# Motherboard_V3_1.net
KiCad netlist of a schematic drawn in EAGLE
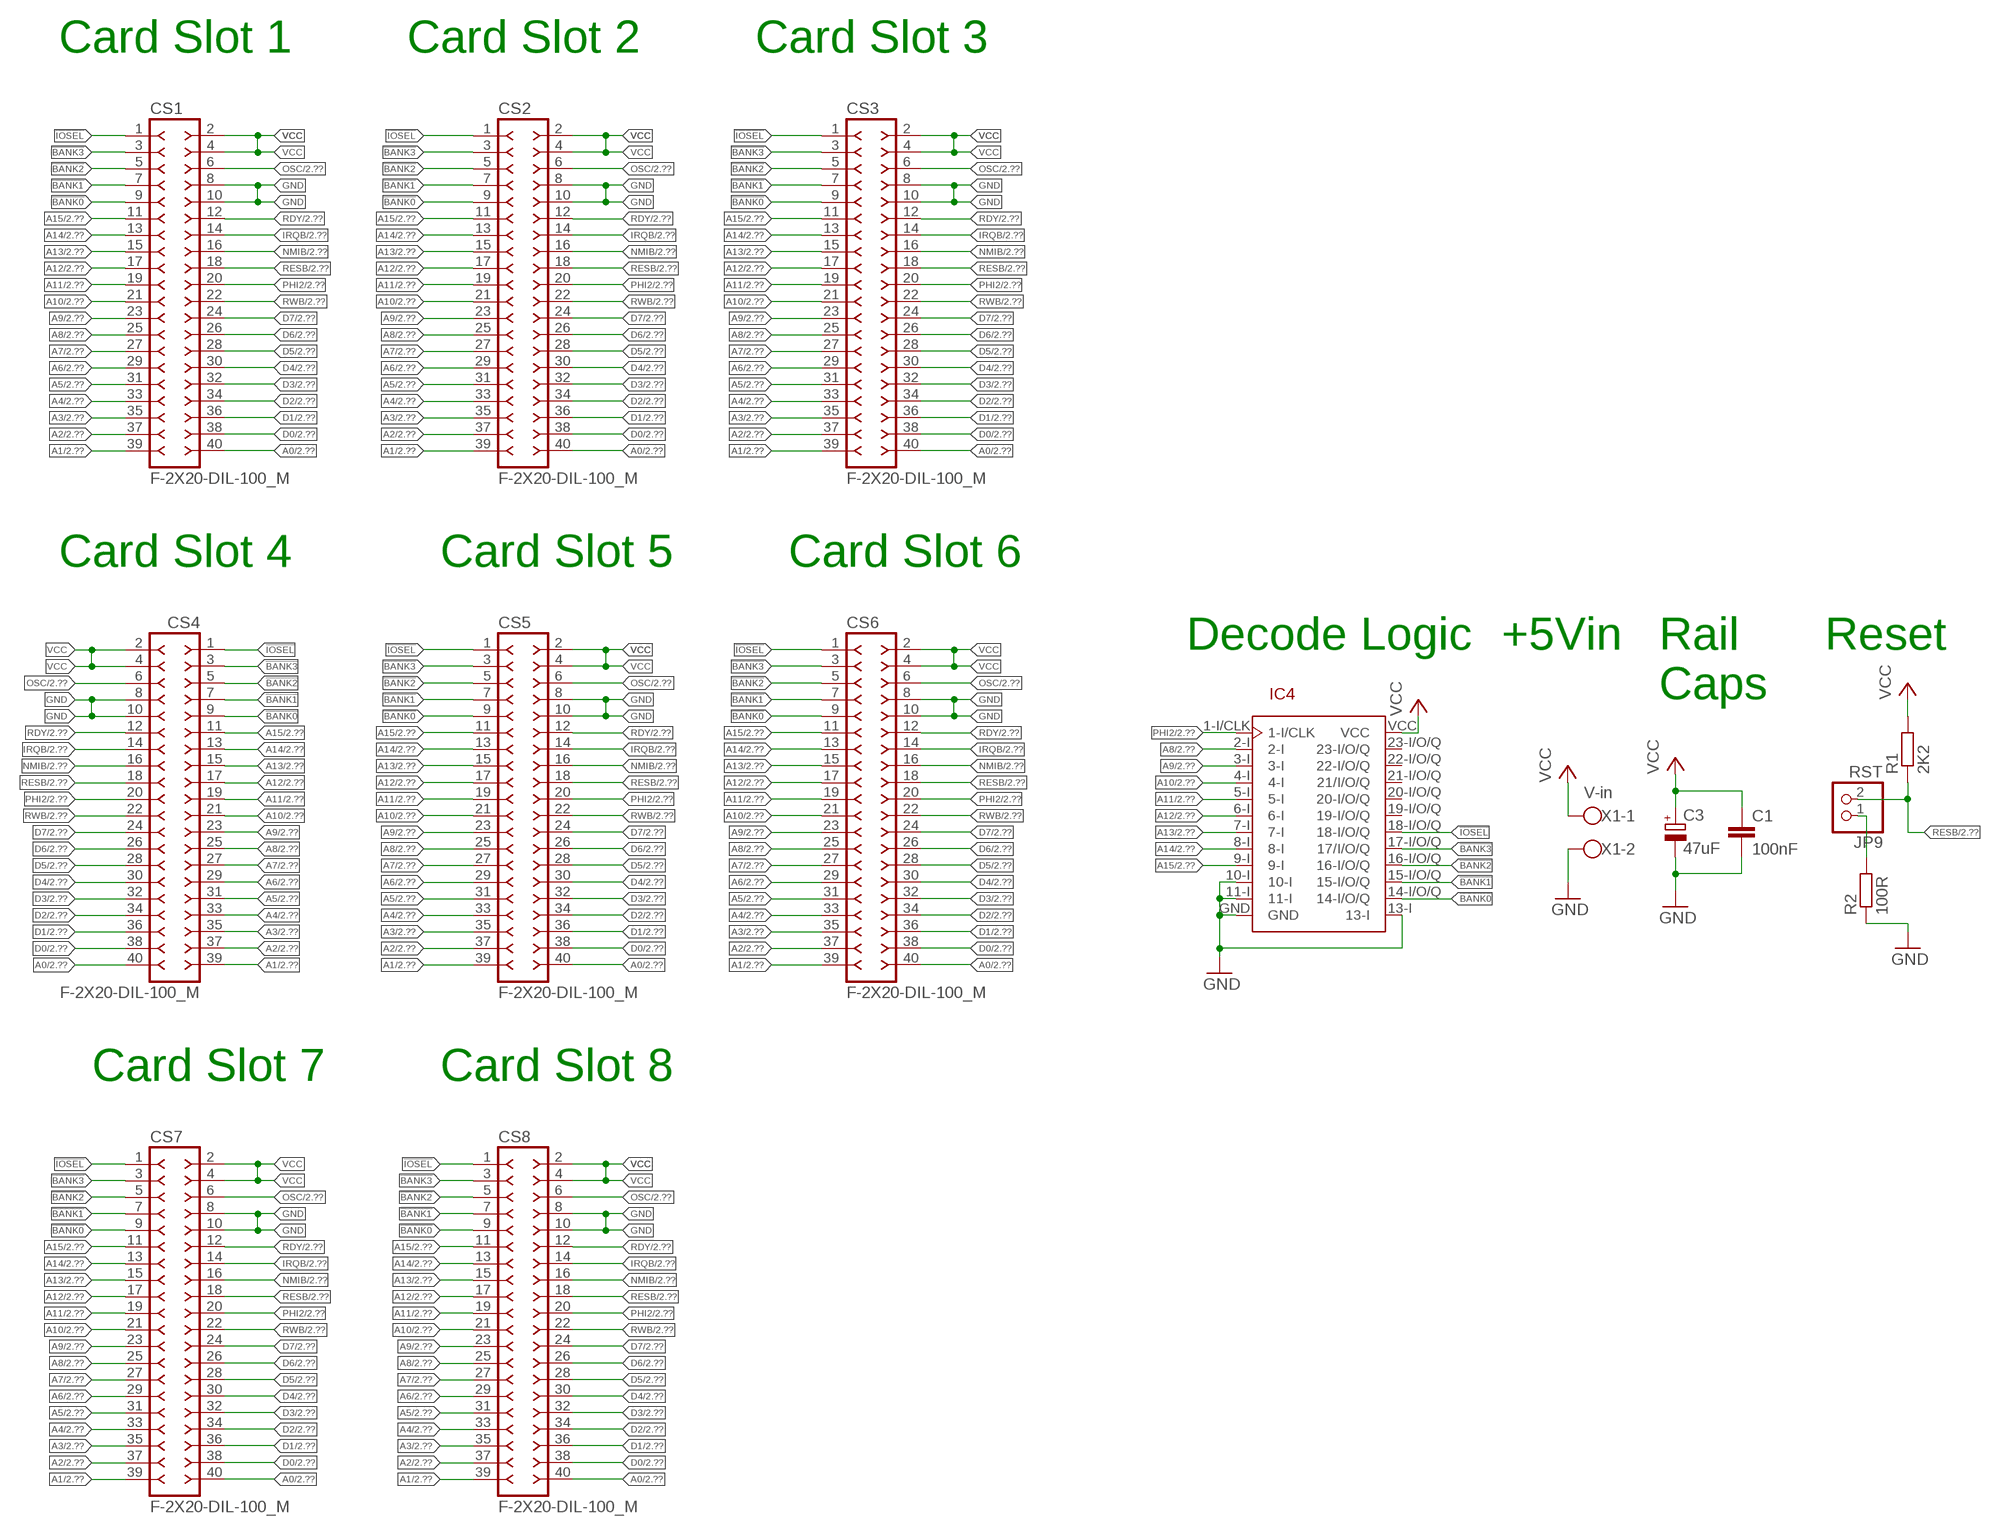
[diagram p0: schematic, sheet 1]
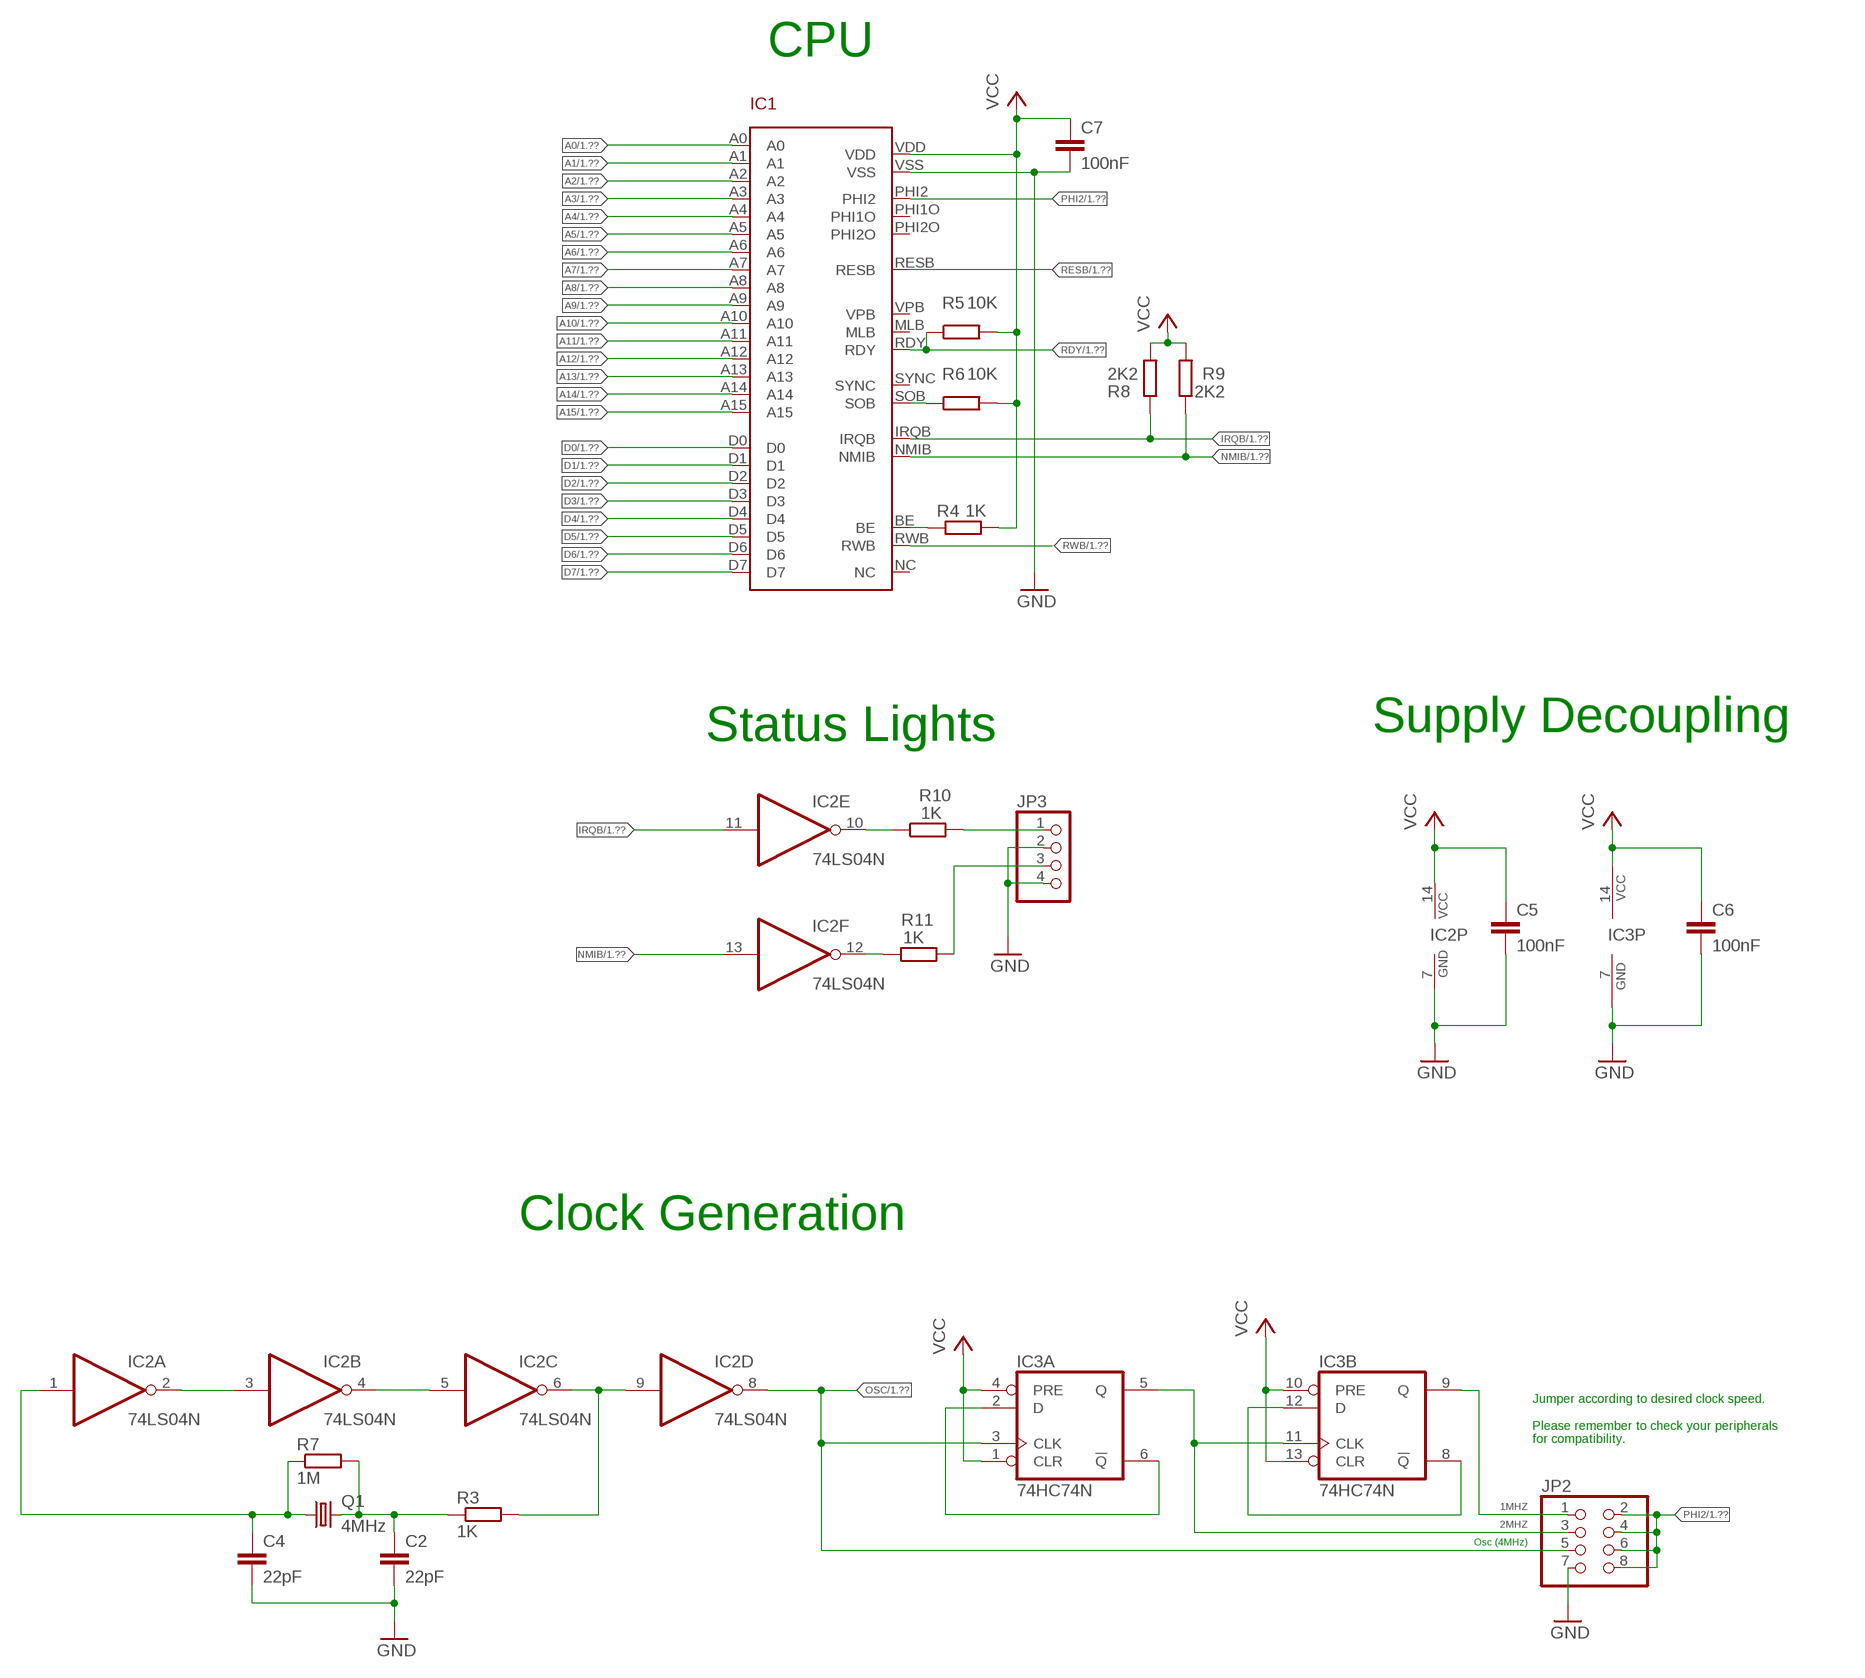
[diagram p1: schematic, sheet 2]

(export (version "E")
  (design (tool "Eeschema 10.0.6"))
  (components
    (comp (ref "C2")
      (value "22pF")
      (footprint "eagle-import:C025-025X050")
      (libsource (lib "eagle-import") (part "C-EU025-025X050"))
    )
    (comp (ref "C4")
      (value "22pF")
      (footprint "eagle-import:C025-025X050")
      (libsource (lib "eagle-import") (part "C-EU025-025X050"))
    )
    (comp (ref "C5")
      (value "100nF")
      (footprint "eagle-import:C050-025X075")
      (libsource (lib "eagle-import") (part "C-EU050-025X075"))
    )
    (comp (ref "C6")
      (value "100nF")
      (footprint "eagle-import:C050-025X075")
      (libsource (lib "eagle-import") (part "C-EU050-025X075"))
    )
    (comp (ref "C7")
      (value "100nF")
      (footprint "eagle-import:C050-025X075")
      (libsource (lib "eagle-import") (part "C-EU050-025X075"))
    )
    (comp (ref "IC1")
      (value "W65C02S-DIP")
      (footprint "eagle-import:DIP40")
      (libsource (lib "eagle-import") (part "W65C02S-DIP"))
    )
    (comp (ref "IC2")
      (value "74LS04N")
      (footprint "eagle-import:DIL14")
      (libsource (lib "eagle-import") (part "7404NHC"))
    )
    (comp (ref "IC3")
      (value "74HC74N")
      (footprint "eagle-import:DIL14")
      (libsource (lib "eagle-import") (part "7474NLS"))
    )
    (comp (ref "JP2")
      (value "PINHD-2X4")
      (footprint "eagle-import:2X04")
      (libsource (lib "eagle-import") (part "PINHD-2X4"))
    )
    (comp (ref "JP3")
      (value "PINHD-1X4")
      (footprint "eagle-import:1X04")
      (libsource (lib "eagle-import") (part "PINHD-1X4"))
    )
    (comp (ref "Q1")
      (value "4MHz")
      (footprint "eagle-import:HC49_S")
      (libsource (lib "eagle-import") (part "CRYSTALHC49S"))
    )
    (comp (ref "R3")
      (value "1K")
      (footprint "eagle-import:0207_2V")
      (libsource (lib "eagle-import") (part "R-EU_0207/2V"))
    )
    (comp (ref "R4")
      (value "1K")
      (footprint "eagle-import:0207_10")
      (libsource (lib "eagle-import") (part "R-EU_0207/10"))
    )
    (comp (ref "R5")
      (value "10K")
      (footprint "eagle-import:0207_2V")
      (libsource (lib "eagle-import") (part "R-EU_0207/2V"))
    )
    (comp (ref "R6")
      (value "10K")
      (footprint "eagle-import:0207_10")
      (libsource (lib "eagle-import") (part "R-EU_0207/10"))
    )
    (comp (ref "R7")
      (value "1M")
      (footprint "eagle-import:0207_2V")
      (libsource (lib "eagle-import") (part "R-EU_0207/2V"))
    )
    (comp (ref "R8")
      (value "2K2")
      (footprint "eagle-import:0207_2V")
      (libsource (lib "eagle-import") (part "R-EU_0207/2V"))
    )
    (comp (ref "R9")
      (value "2K2")
      (footprint "eagle-import:0207_2V")
      (libsource (lib "eagle-import") (part "R-EU_0207/2V"))
    )
    (comp (ref "R10")
      (value "1K")
      (footprint "eagle-import:0207_2V")
      (libsource (lib "eagle-import") (part "R-EU_0207/2V"))
    )
    (comp (ref "R11")
      (value "1K")
      (footprint "eagle-import:0207_2V")
      (libsource (lib "eagle-import") (part "R-EU_0207/2V"))
    )
    (comp (ref "C1")
      (value "100nF")
      (footprint "eagle-import:C050-025X075")
      (libsource (lib "eagle-import") (part "C-EU050-025X075"))
    )
    (comp (ref "C3")
      (value "47uF")
      (footprint "eagle-import:E2,5-7")
      (libsource (lib "eagle-import") (part "CPOL-EUE2.5-7"))
    )
    (comp (ref "CS1")
      (value "F-2X20-DIL-100_M")
      (footprint "eagle-import:DIL-100-2X20_M")
      (libsource (lib "eagle-import") (part "F-2X20-DIL-100_M"))
    )
    (comp (ref "CS2")
      (value "F-2X20-DIL-100_M")
      (footprint "eagle-import:DIL-100-2X20_M")
      (libsource (lib "eagle-import") (part "F-2X20-DIL-100_M"))
    )
    (comp (ref "CS3")
      (value "F-2X20-DIL-100_M")
      (footprint "eagle-import:DIL-100-2X20_M")
      (libsource (lib "eagle-import") (part "F-2X20-DIL-100_M"))
    )
    (comp (ref "CS4")
      (value "F-2X20-DIL-100_M")
      (footprint "eagle-import:DIL-100-2X20_M")
      (libsource (lib "eagle-import") (part "F-2X20-DIL-100_M"))
    )
    (comp (ref "CS5")
      (value "F-2X20-DIL-100_M")
      (footprint "eagle-import:DIL-100-2X20_M")
      (libsource (lib "eagle-import") (part "F-2X20-DIL-100_M"))
    )
    (comp (ref "CS6")
      (value "F-2X20-DIL-100_M")
      (footprint "eagle-import:DIL-100-2X20_M")
      (libsource (lib "eagle-import") (part "F-2X20-DIL-100_M"))
    )
    (comp (ref "CS7")
      (value "F-2X20-DIL-100_M")
      (footprint "eagle-import:DIL-100-2X20_M")
      (libsource (lib "eagle-import") (part "F-2X20-DIL-100_M"))
    )
    (comp (ref "CS8")
      (value "F-2X20-DIL-100_M")
      (footprint "eagle-import:DIL-100-2X20_M")
      (libsource (lib "eagle-import") (part "F-2X20-DIL-100_M"))
    )
    (comp (ref "IC4")
      (value "GAL22V10D-7LP")
      (footprint "eagle-import:DIP24")
      (libsource (lib "eagle-import") (part "GAL22V10D-DIP"))
    )
    (comp (ref "JP9")
      (value "RST")
      (footprint "eagle-import:1X02")
      (libsource (lib "eagle-import") (part "PINHD-1X2"))
    )
    (comp (ref "R1")
      (value "2K2")
      (footprint "eagle-import:0207_10")
      (libsource (lib "eagle-import") (part "R-EU_0207/10"))
    )
    (comp (ref "R2")
      (value "100R")
      (footprint "eagle-import:0207_10")
      (libsource (lib "eagle-import") (part "R-EU_0207/10"))
    )
    (comp (ref "X1")
      (value "V-in")
      (footprint "eagle-import:W237-102")
      (fields (field (name "MPN") "237-102"))
      (libsource (lib "eagle-import") (part "W237-102"))
    )
  )
  (nets
    (net (code "1") (name "1MHZ") (class "Default")
      (node (ref "IC3") (pin "9") (pinfunction "Q_9") (pintype "output"))
      (node (ref "JP2") (pin "1") (pinfunction "1_1") (pintype "passive"))
    )
    (net (code "2") (name "2MHZ") (class "Default")
      (node (ref "IC3") (pin "11") (pinfunction "CLK_11") (pintype "input"))
      (node (ref "IC3") (pin "5") (pinfunction "Q_5") (pintype "output"))
      (node (ref "JP2") (pin "3") (pinfunction "3_3") (pintype "passive"))
    )
    (net (code "3") (name "A0") (class "Default")
      (node (ref "CS1") (pin "40") (pinfunction "40_40") (pintype "passive"))
      (node (ref "CS2") (pin "40") (pinfunction "40_40") (pintype "passive"))
      (node (ref "CS3") (pin "40") (pinfunction "40_40") (pintype "passive"))
      (node (ref "CS4") (pin "40") (pinfunction "40_40") (pintype "passive"))
      (node (ref "CS5") (pin "40") (pinfunction "40_40") (pintype "passive"))
      (node (ref "CS6") (pin "40") (pinfunction "40_40") (pintype "passive"))
      (node (ref "CS7") (pin "40") (pinfunction "40_40") (pintype "passive"))
      (node (ref "CS8") (pin "40") (pinfunction "40_40") (pintype "passive"))
      (node (ref "IC1") (pin "A0") (pinfunction "A0_A0") (pintype "output"))
    )
    (net (code "4") (name "A1") (class "Default")
      (node (ref "CS1") (pin "39") (pinfunction "39_39") (pintype "passive"))
      (node (ref "CS2") (pin "39") (pinfunction "39_39") (pintype "passive"))
      (node (ref "CS3") (pin "39") (pinfunction "39_39") (pintype "passive"))
      (node (ref "CS4") (pin "39") (pinfunction "39_39") (pintype "passive"))
      (node (ref "CS5") (pin "39") (pinfunction "39_39") (pintype "passive"))
      (node (ref "CS6") (pin "39") (pinfunction "39_39") (pintype "passive"))
      (node (ref "CS7") (pin "39") (pinfunction "39_39") (pintype "passive"))
      (node (ref "CS8") (pin "39") (pinfunction "39_39") (pintype "passive"))
      (node (ref "IC1") (pin "A1") (pinfunction "A1_A1") (pintype "output"))
    )
    (net (code "5") (name "A2") (class "Default")
      (node (ref "CS1") (pin "37") (pinfunction "37_37") (pintype "passive"))
      (node (ref "CS2") (pin "37") (pinfunction "37_37") (pintype "passive"))
      (node (ref "CS3") (pin "37") (pinfunction "37_37") (pintype "passive"))
      (node (ref "CS4") (pin "37") (pinfunction "37_37") (pintype "passive"))
      (node (ref "CS5") (pin "37") (pinfunction "37_37") (pintype "passive"))
      (node (ref "CS6") (pin "37") (pinfunction "37_37") (pintype "passive"))
      (node (ref "CS7") (pin "37") (pinfunction "37_37") (pintype "passive"))
      (node (ref "CS8") (pin "37") (pinfunction "37_37") (pintype "passive"))
      (node (ref "IC1") (pin "A2") (pinfunction "A2_A2") (pintype "output"))
    )
    (net (code "6") (name "A3") (class "Default")
      (node (ref "CS1") (pin "35") (pinfunction "35_35") (pintype "passive"))
      (node (ref "CS2") (pin "35") (pinfunction "35_35") (pintype "passive"))
      (node (ref "CS3") (pin "35") (pinfunction "35_35") (pintype "passive"))
      (node (ref "CS4") (pin "35") (pinfunction "35_35") (pintype "passive"))
      (node (ref "CS5") (pin "35") (pinfunction "35_35") (pintype "passive"))
      (node (ref "CS6") (pin "35") (pinfunction "35_35") (pintype "passive"))
      (node (ref "CS7") (pin "35") (pinfunction "35_35") (pintype "passive"))
      (node (ref "CS8") (pin "35") (pinfunction "35_35") (pintype "passive"))
      (node (ref "IC1") (pin "A3") (pinfunction "A3_A3") (pintype "output"))
    )
    (net (code "7") (name "A4") (class "Default")
      (node (ref "CS1") (pin "33") (pinfunction "33_33") (pintype "passive"))
      (node (ref "CS2") (pin "33") (pinfunction "33_33") (pintype "passive"))
      (node (ref "CS3") (pin "33") (pinfunction "33_33") (pintype "passive"))
      (node (ref "CS4") (pin "33") (pinfunction "33_33") (pintype "passive"))
      (node (ref "CS5") (pin "33") (pinfunction "33_33") (pintype "passive"))
      (node (ref "CS6") (pin "33") (pinfunction "33_33") (pintype "passive"))
      (node (ref "CS7") (pin "33") (pinfunction "33_33") (pintype "passive"))
      (node (ref "CS8") (pin "33") (pinfunction "33_33") (pintype "passive"))
      (node (ref "IC1") (pin "A4") (pinfunction "A4_A4") (pintype "output"))
    )
    (net (code "8") (name "A5") (class "Default")
      (node (ref "CS1") (pin "31") (pinfunction "31_31") (pintype "passive"))
      (node (ref "CS2") (pin "31") (pinfunction "31_31") (pintype "passive"))
      (node (ref "CS3") (pin "31") (pinfunction "31_31") (pintype "passive"))
      (node (ref "CS4") (pin "31") (pinfunction "31_31") (pintype "passive"))
      (node (ref "CS5") (pin "31") (pinfunction "31_31") (pintype "passive"))
      (node (ref "CS6") (pin "31") (pinfunction "31_31") (pintype "passive"))
      (node (ref "CS7") (pin "31") (pinfunction "31_31") (pintype "passive"))
      (node (ref "CS8") (pin "31") (pinfunction "31_31") (pintype "passive"))
      (node (ref "IC1") (pin "A5") (pinfunction "A5_A5") (pintype "output"))
    )
    (net (code "9") (name "A6") (class "Default")
      (node (ref "CS1") (pin "29") (pinfunction "29_29") (pintype "passive"))
      (node (ref "CS2") (pin "29") (pinfunction "29_29") (pintype "passive"))
      (node (ref "CS3") (pin "29") (pinfunction "29_29") (pintype "passive"))
      (node (ref "CS4") (pin "29") (pinfunction "29_29") (pintype "passive"))
      (node (ref "CS5") (pin "29") (pinfunction "29_29") (pintype "passive"))
      (node (ref "CS6") (pin "29") (pinfunction "29_29") (pintype "passive"))
      (node (ref "CS7") (pin "29") (pinfunction "29_29") (pintype "passive"))
      (node (ref "CS8") (pin "29") (pinfunction "29_29") (pintype "passive"))
      (node (ref "IC1") (pin "A6") (pinfunction "A6_A6") (pintype "output"))
    )
    (net (code "10") (name "A7") (class "Default")
      (node (ref "CS1") (pin "27") (pinfunction "27_27") (pintype "passive"))
      (node (ref "CS2") (pin "27") (pinfunction "27_27") (pintype "passive"))
      (node (ref "CS3") (pin "27") (pinfunction "27_27") (pintype "passive"))
      (node (ref "CS4") (pin "27") (pinfunction "27_27") (pintype "passive"))
      (node (ref "CS5") (pin "27") (pinfunction "27_27") (pintype "passive"))
      (node (ref "CS6") (pin "27") (pinfunction "27_27") (pintype "passive"))
      (node (ref "CS7") (pin "27") (pinfunction "27_27") (pintype "passive"))
      (node (ref "CS8") (pin "27") (pinfunction "27_27") (pintype "passive"))
      (node (ref "IC1") (pin "A7") (pinfunction "A7_A7") (pintype "output"))
    )
    (net (code "11") (name "A8") (class "Default")
      (node (ref "CS1") (pin "25") (pinfunction "25_25") (pintype "passive"))
      (node (ref "CS2") (pin "25") (pinfunction "25_25") (pintype "passive"))
      (node (ref "CS3") (pin "25") (pinfunction "25_25") (pintype "passive"))
      (node (ref "CS4") (pin "25") (pinfunction "25_25") (pintype "passive"))
      (node (ref "CS5") (pin "25") (pinfunction "25_25") (pintype "passive"))
      (node (ref "CS6") (pin "25") (pinfunction "25_25") (pintype "passive"))
      (node (ref "CS7") (pin "25") (pinfunction "25_25") (pintype "passive"))
      (node (ref "CS8") (pin "25") (pinfunction "25_25") (pintype "passive"))
      (node (ref "IC1") (pin "A8") (pinfunction "A8_A8") (pintype "output"))
      (node (ref "IC4") (pin "2-I") (pinfunction "2-I_2-I") (pintype "input"))
    )
    (net (code "12") (name "A9") (class "Default")
      (node (ref "CS1") (pin "23") (pinfunction "23_23") (pintype "passive"))
      (node (ref "CS2") (pin "23") (pinfunction "23_23") (pintype "passive"))
      (node (ref "CS3") (pin "23") (pinfunction "23_23") (pintype "passive"))
      (node (ref "CS4") (pin "23") (pinfunction "23_23") (pintype "passive"))
      (node (ref "CS5") (pin "23") (pinfunction "23_23") (pintype "passive"))
      (node (ref "CS6") (pin "23") (pinfunction "23_23") (pintype "passive"))
      (node (ref "CS7") (pin "23") (pinfunction "23_23") (pintype "passive"))
      (node (ref "CS8") (pin "23") (pinfunction "23_23") (pintype "passive"))
      (node (ref "IC1") (pin "A9") (pinfunction "A9_A9") (pintype "output"))
      (node (ref "IC4") (pin "3-I") (pinfunction "3-I_3-I") (pintype "input"))
    )
    (net (code "13") (name "A10") (class "Default")
      (node (ref "CS1") (pin "21") (pinfunction "21_21") (pintype "passive"))
      (node (ref "CS2") (pin "21") (pinfunction "21_21") (pintype "passive"))
      (node (ref "CS3") (pin "21") (pinfunction "21_21") (pintype "passive"))
      (node (ref "CS4") (pin "21") (pinfunction "21_21") (pintype "passive"))
      (node (ref "CS5") (pin "21") (pinfunction "21_21") (pintype "passive"))
      (node (ref "CS6") (pin "21") (pinfunction "21_21") (pintype "passive"))
      (node (ref "CS7") (pin "21") (pinfunction "21_21") (pintype "passive"))
      (node (ref "CS8") (pin "21") (pinfunction "21_21") (pintype "passive"))
      (node (ref "IC1") (pin "A10") (pinfunction "A10_A10") (pintype "output"))
      (node (ref "IC4") (pin "4-I") (pinfunction "4-I_4-I") (pintype "input"))
    )
    (net (code "14") (name "A11") (class "Default")
      (node (ref "CS1") (pin "19") (pinfunction "19_19") (pintype "passive"))
      (node (ref "CS2") (pin "19") (pinfunction "19_19") (pintype "passive"))
      (node (ref "CS3") (pin "19") (pinfunction "19_19") (pintype "passive"))
      (node (ref "CS4") (pin "19") (pinfunction "19_19") (pintype "passive"))
      (node (ref "CS5") (pin "19") (pinfunction "19_19") (pintype "passive"))
      (node (ref "CS6") (pin "19") (pinfunction "19_19") (pintype "passive"))
      (node (ref "CS7") (pin "19") (pinfunction "19_19") (pintype "passive"))
      (node (ref "CS8") (pin "19") (pinfunction "19_19") (pintype "passive"))
      (node (ref "IC1") (pin "A11") (pinfunction "A11_A11") (pintype "output"))
      (node (ref "IC4") (pin "5-I") (pinfunction "5-I_5-I") (pintype "input"))
    )
    (net (code "15") (name "A12") (class "Default")
      (node (ref "CS1") (pin "17") (pinfunction "17_17") (pintype "passive"))
      (node (ref "CS2") (pin "17") (pinfunction "17_17") (pintype "passive"))
      (node (ref "CS3") (pin "17") (pinfunction "17_17") (pintype "passive"))
      (node (ref "CS4") (pin "17") (pinfunction "17_17") (pintype "passive"))
      (node (ref "CS5") (pin "17") (pinfunction "17_17") (pintype "passive"))
      (node (ref "CS6") (pin "17") (pinfunction "17_17") (pintype "passive"))
      (node (ref "CS7") (pin "17") (pinfunction "17_17") (pintype "passive"))
      (node (ref "CS8") (pin "17") (pinfunction "17_17") (pintype "passive"))
      (node (ref "IC1") (pin "A12") (pinfunction "A12_A12") (pintype "output"))
      (node (ref "IC4") (pin "6-I") (pinfunction "6-I_6-I") (pintype "input"))
    )
    (net (code "16") (name "A13") (class "Default")
      (node (ref "CS1") (pin "15") (pinfunction "15_15") (pintype "passive"))
      (node (ref "CS2") (pin "15") (pinfunction "15_15") (pintype "passive"))
      (node (ref "CS3") (pin "15") (pinfunction "15_15") (pintype "passive"))
      (node (ref "CS4") (pin "15") (pinfunction "15_15") (pintype "passive"))
      (node (ref "CS5") (pin "15") (pinfunction "15_15") (pintype "passive"))
      (node (ref "CS6") (pin "15") (pinfunction "15_15") (pintype "passive"))
      (node (ref "CS7") (pin "15") (pinfunction "15_15") (pintype "passive"))
      (node (ref "CS8") (pin "15") (pinfunction "15_15") (pintype "passive"))
      (node (ref "IC1") (pin "A13") (pinfunction "A13_A13") (pintype "output"))
      (node (ref "IC4") (pin "7-I") (pinfunction "7-I_7-I") (pintype "input"))
    )
    (net (code "17") (name "A14") (class "Default")
      (node (ref "CS1") (pin "13") (pinfunction "13_13") (pintype "passive"))
      (node (ref "CS2") (pin "13") (pinfunction "13_13") (pintype "passive"))
      (node (ref "CS3") (pin "13") (pinfunction "13_13") (pintype "passive"))
      (node (ref "CS4") (pin "13") (pinfunction "13_13") (pintype "passive"))
      (node (ref "CS5") (pin "13") (pinfunction "13_13") (pintype "passive"))
      (node (ref "CS6") (pin "13") (pinfunction "13_13") (pintype "passive"))
      (node (ref "CS7") (pin "13") (pinfunction "13_13") (pintype "passive"))
      (node (ref "CS8") (pin "13") (pinfunction "13_13") (pintype "passive"))
      (node (ref "IC1") (pin "A14") (pinfunction "A14_A14") (pintype "output"))
      (node (ref "IC4") (pin "8-I") (pinfunction "8-I_8-I") (pintype "input"))
    )
    (net (code "18") (name "A15") (class "Default")
      (node (ref "CS1") (pin "11") (pinfunction "11_11") (pintype "passive"))
      (node (ref "CS2") (pin "11") (pinfunction "11_11") (pintype "passive"))
      (node (ref "CS3") (pin "11") (pinfunction "11_11") (pintype "passive"))
      (node (ref "CS4") (pin "11") (pinfunction "11_11") (pintype "passive"))
      (node (ref "CS5") (pin "11") (pinfunction "11_11") (pintype "passive"))
      (node (ref "CS6") (pin "11") (pinfunction "11_11") (pintype "passive"))
      (node (ref "CS7") (pin "11") (pinfunction "11_11") (pintype "passive"))
      (node (ref "CS8") (pin "11") (pinfunction "11_11") (pintype "passive"))
      (node (ref "IC1") (pin "A15") (pinfunction "A15_A15") (pintype "output"))
      (node (ref "IC4") (pin "9-I") (pinfunction "9-I_9-I") (pintype "input"))
    )
    (net (code "19") (name "D0") (class "Default")
      (node (ref "CS1") (pin "38") (pinfunction "38_38") (pintype "passive"))
      (node (ref "CS2") (pin "38") (pinfunction "38_38") (pintype "passive"))
      (node (ref "CS3") (pin "38") (pinfunction "38_38") (pintype "passive"))
      (node (ref "CS4") (pin "38") (pinfunction "38_38") (pintype "passive"))
      (node (ref "CS5") (pin "38") (pinfunction "38_38") (pintype "passive"))
      (node (ref "CS6") (pin "38") (pinfunction "38_38") (pintype "passive"))
      (node (ref "CS7") (pin "38") (pinfunction "38_38") (pintype "passive"))
      (node (ref "CS8") (pin "38") (pinfunction "38_38") (pintype "passive"))
      (node (ref "IC1") (pin "D0") (pinfunction "D0_D0") (pintype "bidirectional"))
    )
    (net (code "20") (name "D1") (class "Default")
      (node (ref "CS1") (pin "36") (pinfunction "36_36") (pintype "passive"))
      (node (ref "CS2") (pin "36") (pinfunction "36_36") (pintype "passive"))
      (node (ref "CS3") (pin "36") (pinfunction "36_36") (pintype "passive"))
      (node (ref "CS4") (pin "36") (pinfunction "36_36") (pintype "passive"))
      (node (ref "CS5") (pin "36") (pinfunction "36_36") (pintype "passive"))
      (node (ref "CS6") (pin "36") (pinfunction "36_36") (pintype "passive"))
      (node (ref "CS7") (pin "36") (pinfunction "36_36") (pintype "passive"))
      (node (ref "CS8") (pin "36") (pinfunction "36_36") (pintype "passive"))
      (node (ref "IC1") (pin "D1") (pinfunction "D1_D1") (pintype "bidirectional"))
    )
    (net (code "21") (name "D2") (class "Default")
      (node (ref "CS1") (pin "34") (pinfunction "34_34") (pintype "passive"))
      (node (ref "CS2") (pin "34") (pinfunction "34_34") (pintype "passive"))
      (node (ref "CS3") (pin "34") (pinfunction "34_34") (pintype "passive"))
      (node (ref "CS4") (pin "34") (pinfunction "34_34") (pintype "passive"))
      (node (ref "CS5") (pin "34") (pinfunction "34_34") (pintype "passive"))
      (node (ref "CS6") (pin "34") (pinfunction "34_34") (pintype "passive"))
      (node (ref "CS7") (pin "34") (pinfunction "34_34") (pintype "passive"))
      (node (ref "CS8") (pin "34") (pinfunction "34_34") (pintype "passive"))
      (node (ref "IC1") (pin "D2") (pinfunction "D2_D2") (pintype "bidirectional"))
    )
    (net (code "22") (name "D3") (class "Default")
      (node (ref "CS1") (pin "32") (pinfunction "32_32") (pintype "passive"))
      (node (ref "CS2") (pin "32") (pinfunction "32_32") (pintype "passive"))
      (node (ref "CS3") (pin "32") (pinfunction "32_32") (pintype "passive"))
      (node (ref "CS4") (pin "32") (pinfunction "32_32") (pintype "passive"))
      (node (ref "CS5") (pin "32") (pinfunction "32_32") (pintype "passive"))
      (node (ref "CS6") (pin "32") (pinfunction "32_32") (pintype "passive"))
      (node (ref "CS7") (pin "32") (pinfunction "32_32") (pintype "passive"))
      (node (ref "CS8") (pin "32") (pinfunction "32_32") (pintype "passive"))
      (node (ref "IC1") (pin "D3") (pinfunction "D3_D3") (pintype "bidirectional"))
    )
    (net (code "23") (name "D4") (class "Default")
      (node (ref "CS1") (pin "30") (pinfunction "30_30") (pintype "passive"))
      (node (ref "CS2") (pin "30") (pinfunction "30_30") (pintype "passive"))
      (node (ref "CS3") (pin "30") (pinfunction "30_30") (pintype "passive"))
      (node (ref "CS4") (pin "30") (pinfunction "30_30") (pintype "passive"))
      (node (ref "CS5") (pin "30") (pinfunction "30_30") (pintype "passive"))
      (node (ref "CS6") (pin "30") (pinfunction "30_30") (pintype "passive"))
      (node (ref "CS7") (pin "30") (pinfunction "30_30") (pintype "passive"))
      (node (ref "CS8") (pin "30") (pinfunction "30_30") (pintype "passive"))
      (node (ref "IC1") (pin "D4") (pinfunction "D4_D4") (pintype "bidirectional"))
    )
    (net (code "24") (name "D5") (class "Default")
      (node (ref "CS1") (pin "28") (pinfunction "28_28") (pintype "passive"))
      (node (ref "CS2") (pin "28") (pinfunction "28_28") (pintype "passive"))
      (node (ref "CS3") (pin "28") (pinfunction "28_28") (pintype "passive"))
      (node (ref "CS4") (pin "28") (pinfunction "28_28") (pintype "passive"))
      (node (ref "CS5") (pin "28") (pinfunction "28_28") (pintype "passive"))
      (node (ref "CS6") (pin "28") (pinfunction "28_28") (pintype "passive"))
      (node (ref "CS7") (pin "28") (pinfunction "28_28") (pintype "passive"))
      (node (ref "CS8") (pin "28") (pinfunction "28_28") (pintype "passive"))
      (node (ref "IC1") (pin "D5") (pinfunction "D5_D5") (pintype "bidirectional"))
    )
    (net (code "25") (name "D6") (class "Default")
      (node (ref "CS1") (pin "26") (pinfunction "26_26") (pintype "passive"))
      (node (ref "CS2") (pin "26") (pinfunction "26_26") (pintype "passive"))
      (node (ref "CS3") (pin "26") (pinfunction "26_26") (pintype "passive"))
      (node (ref "CS4") (pin "26") (pinfunction "26_26") (pintype "passive"))
      (node (ref "CS5") (pin "26") (pinfunction "26_26") (pintype "passive"))
      (node (ref "CS6") (pin "26") (pinfunction "26_26") (pintype "passive"))
      (node (ref "CS7") (pin "26") (pinfunction "26_26") (pintype "passive"))
      (node (ref "CS8") (pin "26") (pinfunction "26_26") (pintype "passive"))
      (node (ref "IC1") (pin "D6") (pinfunction "D6_D6") (pintype "bidirectional"))
    )
    (net (code "26") (name "D7") (class "Default")
      (node (ref "CS1") (pin "24") (pinfunction "24_24") (pintype "passive"))
      (node (ref "CS2") (pin "24") (pinfunction "24_24") (pintype "passive"))
      (node (ref "CS3") (pin "24") (pinfunction "24_24") (pintype "passive"))
      (node (ref "CS4") (pin "24") (pinfunction "24_24") (pintype "passive"))
      (node (ref "CS5") (pin "24") (pinfunction "24_24") (pintype "passive"))
      (node (ref "CS6") (pin "24") (pinfunction "24_24") (pintype "passive"))
      (node (ref "CS7") (pin "24") (pinfunction "24_24") (pintype "passive"))
      (node (ref "CS8") (pin "24") (pinfunction "24_24") (pintype "passive"))
      (node (ref "IC1") (pin "D7") (pinfunction "D7_D7") (pintype "bidirectional"))
    )
    (net (code "27") (name "GND") (class "Default")
      (node (ref "C1") (pin "2") (pinfunction "2_2") (pintype "passive"))
      (node (ref "C2") (pin "2") (pinfunction "2_2") (pintype "passive"))
      (node (ref "C3") (pin "-") (pinfunction "-_-") (pintype "passive"))
      (node (ref "C4") (pin "2") (pinfunction "2_2") (pintype "passive"))
      (node (ref "C5") (pin "2") (pinfunction "2_2") (pintype "passive"))
      (node (ref "C6") (pin "2") (pinfunction "2_2") (pintype "passive"))
      (node (ref "C7") (pin "2") (pinfunction "2_2") (pintype "passive"))
      (node (ref "CS1") (pin "10") (pinfunction "10_10") (pintype "passive"))
      (node (ref "CS1") (pin "8") (pinfunction "8_8") (pintype "passive"))
      (node (ref "CS2") (pin "10") (pinfunction "10_10") (pintype "passive"))
      (node (ref "CS2") (pin "8") (pinfunction "8_8") (pintype "passive"))
      (node (ref "CS3") (pin "10") (pinfunction "10_10") (pintype "passive"))
      (node (ref "CS3") (pin "8") (pinfunction "8_8") (pintype "passive"))
      (node (ref "CS4") (pin "10") (pinfunction "10_10") (pintype "passive"))
      (node (ref "CS4") (pin "8") (pinfunction "8_8") (pintype "passive"))
      (node (ref "CS5") (pin "10") (pinfunction "10_10") (pintype "passive"))
      (node (ref "CS5") (pin "8") (pinfunction "8_8") (pintype "passive"))
      (node (ref "CS6") (pin "10") (pinfunction "10_10") (pintype "passive"))
      (node (ref "CS6") (pin "8") (pinfunction "8_8") (pintype "passive"))
      (node (ref "CS7") (pin "10") (pinfunction "10_10") (pintype "passive"))
      (node (ref "CS7") (pin "8") (pinfunction "8_8") (pintype "passive"))
      (node (ref "CS8") (pin "10") (pinfunction "10_10") (pintype "passive"))
      (node (ref "CS8") (pin "8") (pinfunction "8_8") (pintype "passive"))
      (node (ref "IC1") (pin "VSS") (pinfunction "VSS_VSS") (pintype "power_in"))
      (node (ref "IC2") (pin "7") (pinfunction "GND_7") (pintype "power_in"))
      (node (ref "IC3") (pin "7") (pinfunction "GND_7") (pintype "power_in"))
      (node (ref "IC4") (pin "10-I") (pinfunction "10-I_10-I") (pintype "input"))
      (node (ref "IC4") (pin "11-I") (pinfunction "11-I_11-I") (pintype "input"))
      (node (ref "IC4") (pin "13-I") (pinfunction "13-I_13-I") (pintype "input"))
      (node (ref "IC4") (pin "GND") (pinfunction "GND_GND") (pintype "power_in"))
      (node (ref "JP2") (pin "7") (pinfunction "7_7") (pintype "passive"))
      (node (ref "JP3") (pin "2") (pinfunction "2_2") (pintype "passive"))
      (node (ref "JP3") (pin "4") (pinfunction "4_4") (pintype "passive"))
      (node (ref "R2") (pin "1") (pinfunction "1_1") (pintype "passive"))
      (node (ref "X1") (pin "2") (pinfunction "KL_2") (pintype "passive"))
    )
    (net (code "28") (name "IRQB") (class "Default")
      (node (ref "CS1") (pin "14") (pinfunction "14_14") (pintype "passive"))
      (node (ref "CS2") (pin "14") (pinfunction "14_14") (pintype "passive"))
      (node (ref "CS3") (pin "14") (pinfunction "14_14") (pintype "passive"))
      (node (ref "CS4") (pin "14") (pinfunction "14_14") (pintype "passive"))
      (node (ref "CS5") (pin "14") (pinfunction "14_14") (pintype "passive"))
      (node (ref "CS6") (pin "14") (pinfunction "14_14") (pintype "passive"))
      (node (ref "CS7") (pin "14") (pinfunction "14_14") (pintype "passive"))
      (node (ref "CS8") (pin "14") (pinfunction "14_14") (pintype "passive"))
      (node (ref "IC1") (pin "IRQB") (pinfunction "IRQB_IRQB") (pintype "input"))
      (node (ref "IC2") (pin "11") (pinfunction "I_11") (pintype "input"))
      (node (ref "R8") (pin "1") (pinfunction "1_1") (pintype "passive"))
    )
    (net (code "29") (name "NMIB") (class "Default")
      (node (ref "CS1") (pin "16") (pinfunction "16_16") (pintype "passive"))
      (node (ref "CS2") (pin "16") (pinfunction "16_16") (pintype "passive"))
      (node (ref "CS3") (pin "16") (pinfunction "16_16") (pintype "passive"))
      (node (ref "CS4") (pin "16") (pinfunction "16_16") (pintype "passive"))
      (node (ref "CS5") (pin "16") (pinfunction "16_16") (pintype "passive"))
      (node (ref "CS6") (pin "16") (pinfunction "16_16") (pintype "passive"))
      (node (ref "CS7") (pin "16") (pinfunction "16_16") (pintype "passive"))
      (node (ref "CS8") (pin "16") (pinfunction "16_16") (pintype "passive"))
      (node (ref "IC1") (pin "NMIB") (pinfunction "NMIB_NMIB") (pintype "input"))
      (node (ref "IC2") (pin "13") (pinfunction "I_13") (pintype "input"))
      (node (ref "R9") (pin "1") (pinfunction "1_1") (pintype "passive"))
    )
    (net (code "30") (name "Net-(C2-Pad1)") (class "Default")
      (node (ref "C2") (pin "1") (pinfunction "1_1") (pintype "passive"))
      (node (ref "Q1") (pin "2") (pinfunction "2_2") (pintype "passive"))
      (node (ref "R3") (pin "1") (pinfunction "1_1") (pintype "passive"))
      (node (ref "R7") (pin "2") (pinfunction "2_2") (pintype "passive"))
    )
    (net (code "31") (name "Net-(IC1-PadBE)") (class "Default")
      (node (ref "IC1") (pin "BE") (pinfunction "BE_BE") (pintype "input"))
      (node (ref "R4") (pin "1") (pinfunction "1_1") (pintype "passive"))
    )
    (net (code "32") (name "Net-(IC1-PadSOB)") (class "Default")
      (node (ref "IC1") (pin "SOB") (pinfunction "SOB_SOB") (pintype "input"))
      (node (ref "R6") (pin "1") (pinfunction "1_1") (pintype "passive"))
    )
    (net (code "33") (name "Net-(IC2A-I)") (class "Default")
      (node (ref "C4") (pin "1") (pinfunction "1_1") (pintype "passive"))
      (node (ref "IC2") (pin "1") (pinfunction "I_1") (pintype "input"))
      (node (ref "Q1") (pin "1") (pinfunction "1_1") (pintype "passive"))
      (node (ref "R7") (pin "1") (pinfunction "1_1") (pintype "passive"))
    )
    (net (code "34") (name "Net-(IC2A-O)") (class "Default")
      (node (ref "IC2") (pin "2") (pinfunction "O_2") (pintype "output"))
      (node (ref "IC2") (pin "3") (pinfunction "I_3") (pintype "input"))
    )
    (net (code "35") (name "Net-(IC2B-O)") (class "Default")
      (node (ref "IC2") (pin "4") (pinfunction "O_4") (pintype "output"))
      (node (ref "IC2") (pin "5") (pinfunction "I_5") (pintype "input"))
    )
    (net (code "36") (name "Net-(IC2C-O)") (class "Default")
      (node (ref "IC2") (pin "6") (pinfunction "O_6") (pintype "output"))
      (node (ref "IC2") (pin "9") (pinfunction "I_9") (pintype "input"))
      (node (ref "R3") (pin "2") (pinfunction "2_2") (pintype "passive"))
    )
    (net (code "37") (name "Net-(IC2E-O)") (class "Default")
      (node (ref "IC2") (pin "10") (pinfunction "O_10") (pintype "output"))
      (node (ref "R10") (pin "1") (pinfunction "1_1") (pintype "passive"))
    )
    (net (code "38") (name "Net-(IC2F-O)") (class "Default")
      (node (ref "IC2") (pin "12") (pinfunction "O_12") (pintype "output"))
      (node (ref "R11") (pin "1") (pinfunction "1_1") (pintype "passive"))
    )
    (net (code "39") (name "Net-(IC3A-D)") (class "Default")
      (node (ref "IC3") (pin "2") (pinfunction "D_2") (pintype "input"))
      (node (ref "IC3") (pin "6") (pinfunction "~{Q}_6") (pintype "output"))
    )
    (net (code "40") (name "Net-(IC3B-D)") (class "Default")
      (node (ref "IC3") (pin "12") (pinfunction "D_12") (pintype "input"))
      (node (ref "IC3") (pin "8") (pinfunction "~{Q}_8") (pintype "output"))
    )
    (net (code "41") (name "Net-(JP3-Pad1)") (class "Default")
      (node (ref "JP3") (pin "1") (pinfunction "1_1") (pintype "passive"))
      (node (ref "R10") (pin "2") (pinfunction "2_2") (pintype "passive"))
    )
    (net (code "42") (name "Net-(JP3-Pad3)") (class "Default")
      (node (ref "JP3") (pin "3") (pinfunction "3_3") (pintype "passive"))
      (node (ref "R11") (pin "2") (pinfunction "2_2") (pintype "passive"))
    )
    (net (code "43") (name "Net-(JP9-Pad1)") (class "Default")
      (node (ref "JP9") (pin "1") (pinfunction "1_1") (pintype "passive"))
      (node (ref "R2") (pin "2") (pinfunction "2_2") (pintype "passive"))
    )
    (net (code "44") (name "OSC") (class "Default")
      (node (ref "CS1") (pin "6") (pinfunction "6_6") (pintype "passive"))
      (node (ref "CS2") (pin "6") (pinfunction "6_6") (pintype "passive"))
      (node (ref "CS3") (pin "6") (pinfunction "6_6") (pintype "passive"))
      (node (ref "CS4") (pin "6") (pinfunction "6_6") (pintype "passive"))
      (node (ref "CS5") (pin "6") (pinfunction "6_6") (pintype "passive"))
      (node (ref "CS6") (pin "6") (pinfunction "6_6") (pintype "passive"))
      (node (ref "CS7") (pin "6") (pinfunction "6_6") (pintype "passive"))
      (node (ref "CS8") (pin "6") (pinfunction "6_6") (pintype "passive"))
      (node (ref "IC2") (pin "8") (pinfunction "O_8") (pintype "output"))
      (node (ref "IC3") (pin "3") (pinfunction "CLK_3") (pintype "input"))
      (node (ref "JP2") (pin "5") (pinfunction "5_5") (pintype "passive"))
    )
    (net (code "45") (name "PHI2") (class "Default")
      (node (ref "CS1") (pin "20") (pinfunction "20_20") (pintype "passive"))
      (node (ref "CS2") (pin "20") (pinfunction "20_20") (pintype "passive"))
      (node (ref "CS3") (pin "20") (pinfunction "20_20") (pintype "passive"))
      (node (ref "CS4") (pin "20") (pinfunction "20_20") (pintype "passive"))
      (node (ref "CS5") (pin "20") (pinfunction "20_20") (pintype "passive"))
      (node (ref "CS6") (pin "20") (pinfunction "20_20") (pintype "passive"))
      (node (ref "CS7") (pin "20") (pinfunction "20_20") (pintype "passive"))
      (node (ref "CS8") (pin "20") (pinfunction "20_20") (pintype "passive"))
      (node (ref "IC1") (pin "PHI2") (pinfunction "PHI2_PHI2") (pintype "input"))
      (node (ref "IC4") (pin "1-I/CLK") (pinfunction "1-I/CLK_1-I/CLK") (pintype "input"))
      (node (ref "JP2") (pin "2") (pinfunction "2_2") (pintype "passive"))
      (node (ref "JP2") (pin "4") (pinfunction "4_4") (pintype "passive"))
      (node (ref "JP2") (pin "6") (pinfunction "6_6") (pintype "passive"))
      (node (ref "JP2") (pin "8") (pinfunction "8_8") (pintype "passive"))
    )
    (net (code "46") (name "RDY") (class "Default")
      (node (ref "CS1") (pin "12") (pinfunction "12_12") (pintype "passive"))
      (node (ref "CS2") (pin "12") (pinfunction "12_12") (pintype "passive"))
      (node (ref "CS3") (pin "12") (pinfunction "12_12") (pintype "passive"))
      (node (ref "CS4") (pin "12") (pinfunction "12_12") (pintype "passive"))
      (node (ref "CS5") (pin "12") (pinfunction "12_12") (pintype "passive"))
      (node (ref "CS6") (pin "12") (pinfunction "12_12") (pintype "passive"))
      (node (ref "CS7") (pin "12") (pinfunction "12_12") (pintype "passive"))
      (node (ref "CS8") (pin "12") (pinfunction "12_12") (pintype "passive"))
      (node (ref "IC1") (pin "RDY") (pinfunction "RDY_RDY") (pintype "input"))
      (node (ref "R5") (pin "1") (pinfunction "1_1") (pintype "passive"))
    )
    (net (code "47") (name "RESB") (class "Default")
      (node (ref "CS1") (pin "18") (pinfunction "18_18") (pintype "passive"))
      (node (ref "CS2") (pin "18") (pinfunction "18_18") (pintype "passive"))
      (node (ref "CS3") (pin "18") (pinfunction "18_18") (pintype "passive"))
      (node (ref "CS4") (pin "18") (pinfunction "18_18") (pintype "passive"))
      (node (ref "CS5") (pin "18") (pinfunction "18_18") (pintype "passive"))
      (node (ref "CS6") (pin "18") (pinfunction "18_18") (pintype "passive"))
      (node (ref "CS7") (pin "18") (pinfunction "18_18") (pintype "passive"))
      (node (ref "CS8") (pin "18") (pinfunction "18_18") (pintype "passive"))
      (node (ref "IC1") (pin "RESB") (pinfunction "RESB_RESB") (pintype "input"))
      (node (ref "JP9") (pin "2") (pinfunction "2_2") (pintype "passive"))
      (node (ref "R1") (pin "1") (pinfunction "1_1") (pintype "passive"))
    )
    (net (code "48") (name "RWB") (class "Default")
      (node (ref "CS1") (pin "22") (pinfunction "22_22") (pintype "passive"))
      (node (ref "CS2") (pin "22") (pinfunction "22_22") (pintype "passive"))
      (node (ref "CS3") (pin "22") (pinfunction "22_22") (pintype "passive"))
      (node (ref "CS4") (pin "22") (pinfunction "22_22") (pintype "passive"))
      (node (ref "CS5") (pin "22") (pinfunction "22_22") (pintype "passive"))
      (node (ref "CS6") (pin "22") (pinfunction "22_22") (pintype "passive"))
      (node (ref "CS7") (pin "22") (pinfunction "22_22") (pintype "passive"))
      (node (ref "CS8") (pin "22") (pinfunction "22_22") (pintype "passive"))
      (node (ref "IC1") (pin "RWB") (pinfunction "RWB_RWB") (pintype "output"))
    )
    (net (code "49") (name "VCC") (class "Default")
      (node (ref "C1") (pin "1") (pinfunction "1_1") (pintype "passive"))
      (node (ref "C3") (pin "+") (pinfunction "+_+") (pintype "passive"))
      (node (ref "C5") (pin "1") (pinfunction "1_1") (pintype "passive"))
      (node (ref "C6") (pin "1") (pinfunction "1_1") (pintype "passive"))
      (node (ref "C7") (pin "1") (pinfunction "1_1") (pintype "passive"))
      (node (ref "CS1") (pin "2") (pinfunction "2_2") (pintype "passive"))
      (node (ref "CS1") (pin "4") (pinfunction "4_4") (pintype "passive"))
      (node (ref "CS2") (pin "2") (pinfunction "2_2") (pintype "passive"))
      (node (ref "CS2") (pin "4") (pinfunction "4_4") (pintype "passive"))
      (node (ref "CS3") (pin "2") (pinfunction "2_2") (pintype "passive"))
      (node (ref "CS3") (pin "4") (pinfunction "4_4") (pintype "passive"))
      (node (ref "CS4") (pin "2") (pinfunction "2_2") (pintype "passive"))
      (node (ref "CS4") (pin "4") (pinfunction "4_4") (pintype "passive"))
      (node (ref "CS5") (pin "2") (pinfunction "2_2") (pintype "passive"))
      (node (ref "CS5") (pin "4") (pinfunction "4_4") (pintype "passive"))
      (node (ref "CS6") (pin "2") (pinfunction "2_2") (pintype "passive"))
      (node (ref "CS6") (pin "4") (pinfunction "4_4") (pintype "passive"))
      (node (ref "CS7") (pin "2") (pinfunction "2_2") (pintype "passive"))
      (node (ref "CS7") (pin "4") (pinfunction "4_4") (pintype "passive"))
      (node (ref "CS8") (pin "2") (pinfunction "2_2") (pintype "passive"))
      (node (ref "CS8") (pin "4") (pinfunction "4_4") (pintype "passive"))
      (node (ref "IC1") (pin "VDD") (pinfunction "VDD_VDD") (pintype "power_in"))
      (node (ref "IC2") (pin "14") (pinfunction "VCC_14") (pintype "power_in"))
      (node (ref "IC3") (pin "1") (pinfunction "CLR_1") (pintype "input"))
      (node (ref "IC3") (pin "10") (pinfunction "PRE_10") (pintype "input"))
      (node (ref "IC3") (pin "13") (pinfunction "CLR_13") (pintype "input"))
      (node (ref "IC3") (pin "14") (pinfunction "VCC_14") (pintype "power_in"))
      (node (ref "IC3") (pin "4") (pinfunction "PRE_4") (pintype "input"))
      (node (ref "IC4") (pin "VCC") (pinfunction "VCC_VCC") (pintype "power_in"))
      (node (ref "R1") (pin "2") (pinfunction "2_2") (pintype "passive"))
      (node (ref "R4") (pin "2") (pinfunction "2_2") (pintype "passive"))
      (node (ref "R5") (pin "2") (pinfunction "2_2") (pintype "passive"))
      (node (ref "R6") (pin "2") (pinfunction "2_2") (pintype "passive"))
      (node (ref "R8") (pin "2") (pinfunction "2_2") (pintype "passive"))
      (node (ref "R9") (pin "2") (pinfunction "2_2") (pintype "passive"))
      (node (ref "X1") (pin "1") (pinfunction "KL_1") (pintype "passive"))
    )
    (net (code "50") (name "unconnected-(IC1-PadMLB)") (class "Default")
      (node (ref "IC1") (pin "MLB") (pinfunction "MLB_MLB") (pintype "output"))
    )
    (net (code "51") (name "unconnected-(IC1-PadNC)") (class "Default")
      (node (ref "IC1") (pin "NC") (pinfunction "NC_NC") (pintype "no_connect"))
    )
    (net (code "52") (name "unconnected-(IC1-PadPHI1O)") (class "Default")
      (node (ref "IC1") (pin "PHI1O") (pinfunction "PHI1O_PHI1O") (pintype "output"))
    )
    (net (code "53") (name "unconnected-(IC1-PadPHI2O)") (class "Default")
      (node (ref "IC1") (pin "PHI2O") (pinfunction "PHI2O_PHI2O") (pintype "output"))
    )
    (net (code "54") (name "unconnected-(IC1-PadSYNC)") (class "Default")
      (node (ref "IC1") (pin "SYNC") (pinfunction "SYNC_SYNC") (pintype "output"))
    )
    (net (code "55") (name "unconnected-(IC1-PadVPB)") (class "Default")
      (node (ref "IC1") (pin "VPB") (pinfunction "VPB_VPB") (pintype "output"))
    )
    (net (code "56") (name "unconnected-(IC4-21{slash}I{slash}O{slash}Q-Pad21-I{slash}O{slash}Q)") (class "Default")
      (node (ref "IC4") (pin "21-I/O/Q") (pinfunction "21/I/O/Q_21-I/O/Q") (pintype "bidirectional"))
    )
    (net (code "57") (name "unconnected-(IC4-Pad19-I{slash}O{slash}Q)") (class "Default")
      (node (ref "IC4") (pin "19-I/O/Q") (pinfunction "19-I/O/Q_19-I/O/Q") (pintype "bidirectional"))
    )
    (net (code "58") (name "unconnected-(IC4-Pad20-I{slash}O{slash}Q)") (class "Default")
      (node (ref "IC4") (pin "20-I/O/Q") (pinfunction "20-I/O/Q_20-I/O/Q") (pintype "bidirectional"))
    )
    (net (code "59") (name "unconnected-(IC4-Pad22-I{slash}O{slash}Q)") (class "Default")
      (node (ref "IC4") (pin "22-I/O/Q") (pinfunction "22-I/O/Q_22-I/O/Q") (pintype "bidirectional"))
    )
    (net (code "60") (name "unconnected-(IC4-Pad23-I{slash}O{slash}Q)") (class "Default")
      (node (ref "IC4") (pin "23-I/O/Q") (pinfunction "23-I/O/Q_23-I/O/Q") (pintype "bidirectional"))
    )
    (net (code "61") (name "~{BANK0}") (class "Default")
      (node (ref "CS1") (pin "9") (pinfunction "9_9") (pintype "passive"))
      (node (ref "CS2") (pin "9") (pinfunction "9_9") (pintype "passive"))
      (node (ref "CS3") (pin "9") (pinfunction "9_9") (pintype "passive"))
      (node (ref "CS4") (pin "9") (pinfunction "9_9") (pintype "passive"))
      (node (ref "CS5") (pin "9") (pinfunction "9_9") (pintype "passive"))
      (node (ref "CS6") (pin "9") (pinfunction "9_9") (pintype "passive"))
      (node (ref "CS7") (pin "9") (pinfunction "9_9") (pintype "passive"))
      (node (ref "CS8") (pin "9") (pinfunction "9_9") (pintype "passive"))
      (node (ref "IC4") (pin "14-I/O/Q") (pinfunction "14-I/O/Q_14-I/O/Q") (pintype "bidirectional"))
    )
    (net (code "62") (name "~{BANK1}") (class "Default")
      (node (ref "CS1") (pin "7") (pinfunction "7_7") (pintype "passive"))
      (node (ref "CS2") (pin "7") (pinfunction "7_7") (pintype "passive"))
      (node (ref "CS3") (pin "7") (pinfunction "7_7") (pintype "passive"))
      (node (ref "CS4") (pin "7") (pinfunction "7_7") (pintype "passive"))
      (node (ref "CS5") (pin "7") (pinfunction "7_7") (pintype "passive"))
      (node (ref "CS6") (pin "7") (pinfunction "7_7") (pintype "passive"))
      (node (ref "CS7") (pin "7") (pinfunction "7_7") (pintype "passive"))
      (node (ref "CS8") (pin "7") (pinfunction "7_7") (pintype "passive"))
      (node (ref "IC4") (pin "15-I/O/Q") (pinfunction "15-I/O/Q_15-I/O/Q") (pintype "bidirectional"))
    )
    (net (code "63") (name "~{BANK2}") (class "Default")
      (node (ref "CS1") (pin "5") (pinfunction "5_5") (pintype "passive"))
      (node (ref "CS2") (pin "5") (pinfunction "5_5") (pintype "passive"))
      (node (ref "CS3") (pin "5") (pinfunction "5_5") (pintype "passive"))
      (node (ref "CS4") (pin "5") (pinfunction "5_5") (pintype "passive"))
      (node (ref "CS5") (pin "5") (pinfunction "5_5") (pintype "passive"))
      (node (ref "CS6") (pin "5") (pinfunction "5_5") (pintype "passive"))
      (node (ref "CS7") (pin "5") (pinfunction "5_5") (pintype "passive"))
      (node (ref "CS8") (pin "5") (pinfunction "5_5") (pintype "passive"))
      (node (ref "IC4") (pin "16-I/O/Q") (pinfunction "16-I/O/Q_16-I/O/Q") (pintype "bidirectional"))
    )
    (net (code "64") (name "~{BANK3}") (class "Default")
      (node (ref "CS1") (pin "3") (pinfunction "3_3") (pintype "passive"))
      (node (ref "CS2") (pin "3") (pinfunction "3_3") (pintype "passive"))
      (node (ref "CS3") (pin "3") (pinfunction "3_3") (pintype "passive"))
      (node (ref "CS4") (pin "3") (pinfunction "3_3") (pintype "passive"))
      (node (ref "CS5") (pin "3") (pinfunction "3_3") (pintype "passive"))
      (node (ref "CS6") (pin "3") (pinfunction "3_3") (pintype "passive"))
      (node (ref "CS7") (pin "3") (pinfunction "3_3") (pintype "passive"))
      (node (ref "CS8") (pin "3") (pinfunction "3_3") (pintype "passive"))
      (node (ref "IC4") (pin "17-I/O/Q") (pinfunction "17/I/O/Q_17-I/O/Q") (pintype "bidirectional"))
    )
    (net (code "65") (name "~{IOSEL}") (class "Default")
      (node (ref "CS1") (pin "1") (pinfunction "1_1") (pintype "passive"))
      (node (ref "CS2") (pin "1") (pinfunction "1_1") (pintype "passive"))
      (node (ref "CS3") (pin "1") (pinfunction "1_1") (pintype "passive"))
      (node (ref "CS4") (pin "1") (pinfunction "1_1") (pintype "passive"))
      (node (ref "CS5") (pin "1") (pinfunction "1_1") (pintype "passive"))
      (node (ref "CS6") (pin "1") (pinfunction "1_1") (pintype "passive"))
      (node (ref "CS7") (pin "1") (pinfunction "1_1") (pintype "passive"))
      (node (ref "CS8") (pin "1") (pinfunction "1_1") (pintype "passive"))
      (node (ref "IC4") (pin "18-I/O/Q") (pinfunction "18-I/O/Q_18-I/O/Q") (pintype "bidirectional"))
    )
  )
)
